# TMP100_SMD_TO_HDR.net
KiCad netlist of a schematic drawn in Altium Designer
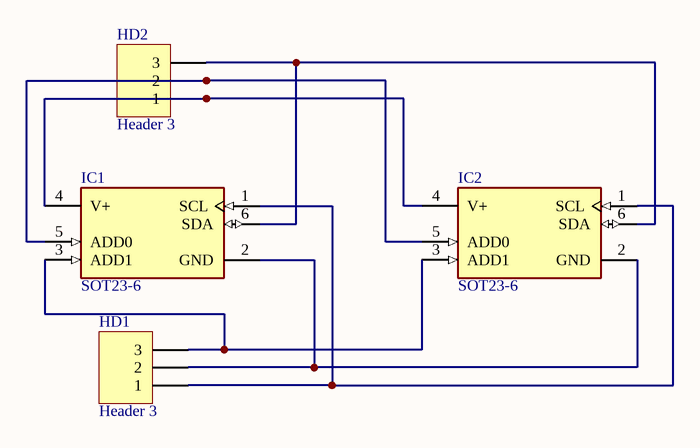
[diagram p0: TMP100_SMD_TO_HDR.SchDoc]

(export (version "E")
  (design (tool "Eeschema 10.0.6"))
  (components
    (comp (ref "HD1")
      (value "Header 3")
      (footprint "HDR1X3")
      (description "Header, 3-Pin")
      (fields (field (name "PUBLISHER") "Altium Limited"))
      (libsource (lib "Miscellaneous Connectors") (part "Header 3"))
    )
    (comp (ref "HD2")
      (value "Header 3")
      (footprint "HDR1X3")
      (description "Header, 3-Pin")
      (fields (field (name "PUBLISHER") "Altium Limited"))
      (libsource (lib "Miscellaneous Connectors") (part "Header 3"))
    )
    (comp (ref "IC1")
      (value "SOT23-6")
      (footprint "FP-DBV0006A-MFG")
      (description "SENSOR DIGITAL -55C-125C SOT23-6")
      (fields
        (field (name "MANUFACTURER PART NUMBER") "TMP100NA/3K")
        (field (name "MANUFACTURER") "Texas Instruments")
      )
      (libsource (lib "Altium Content Vault") (part "08e303d060f057d0a9093fc1030cfeb"))
    )
    (comp (ref "IC2")
      (value "SOT23-6")
      (footprint "FP-DBV0006A-MFG")
      (description "SENSOR DIGITAL -55C-125C SOT23-6")
      (fields
        (field (name "MANUFACTURER PART NUMBER") "TMP100NA/3K")
        (field (name "MANUFACTURER") "Texas Instruments")
      )
      (libsource (lib "Altium Content Vault") (part "08e303d060f057d0a9093fc1030cfeb"))
    )
  )
  (nets
    (net (code "1") (name "Net-(IC1-ADD0)") (class "Default")
      (node (ref "HD2") (pin "2") (pinfunction "2_2") (pintype "passive"))
      (node (ref "IC1") (pin "5") (pinfunction "ADD0_5") (pintype "input"))
      (node (ref "IC2") (pin "5") (pinfunction "ADD0_5") (pintype "input"))
    )
    (net (code "2") (name "Net-(IC1-ADD1)") (class "Default")
      (node (ref "HD1") (pin "3") (pinfunction "3_3") (pintype "passive"))
      (node (ref "IC1") (pin "3") (pinfunction "ADD1_3") (pintype "input"))
      (node (ref "IC2") (pin "3") (pinfunction "ADD1_3") (pintype "input"))
    )
    (net (code "3") (name "Net-(IC1-GND)") (class "Default")
      (node (ref "HD1") (pin "2") (pinfunction "2_2") (pintype "passive"))
      (node (ref "IC1") (pin "2") (pinfunction "GND_2") (pintype "power_in"))
      (node (ref "IC2") (pin "2") (pinfunction "GND_2") (pintype "power_in"))
    )
    (net (code "4") (name "Net-(IC1-SCL)") (class "Default")
      (node (ref "HD1") (pin "1") (pinfunction "1_1") (pintype "passive"))
      (node (ref "IC1") (pin "1") (pinfunction "SCL_1") (pintype "input"))
      (node (ref "IC2") (pin "1") (pinfunction "SCL_1") (pintype "input"))
    )
    (net (code "5") (name "Net-(IC1-SDA)") (class "Default")
      (node (ref "HD2") (pin "3") (pinfunction "3_3") (pintype "passive"))
      (node (ref "IC1") (pin "6") (pinfunction "SDA_6") (pintype "bidirectional"))
      (node (ref "IC2") (pin "6") (pinfunction "SDA_6") (pintype "bidirectional"))
    )
    (net (code "6") (name "Net-(IC1-V+)") (class "Default")
      (node (ref "HD2") (pin "1") (pinfunction "1_1") (pintype "passive"))
      (node (ref "IC1") (pin "4") (pinfunction "V+_4") (pintype "power_in"))
      (node (ref "IC2") (pin "4") (pinfunction "V+_4") (pintype "power_in"))
    )
  )
)
